# 1_Supply.net
KiCad netlist of a schematic drawn in Altium Designer
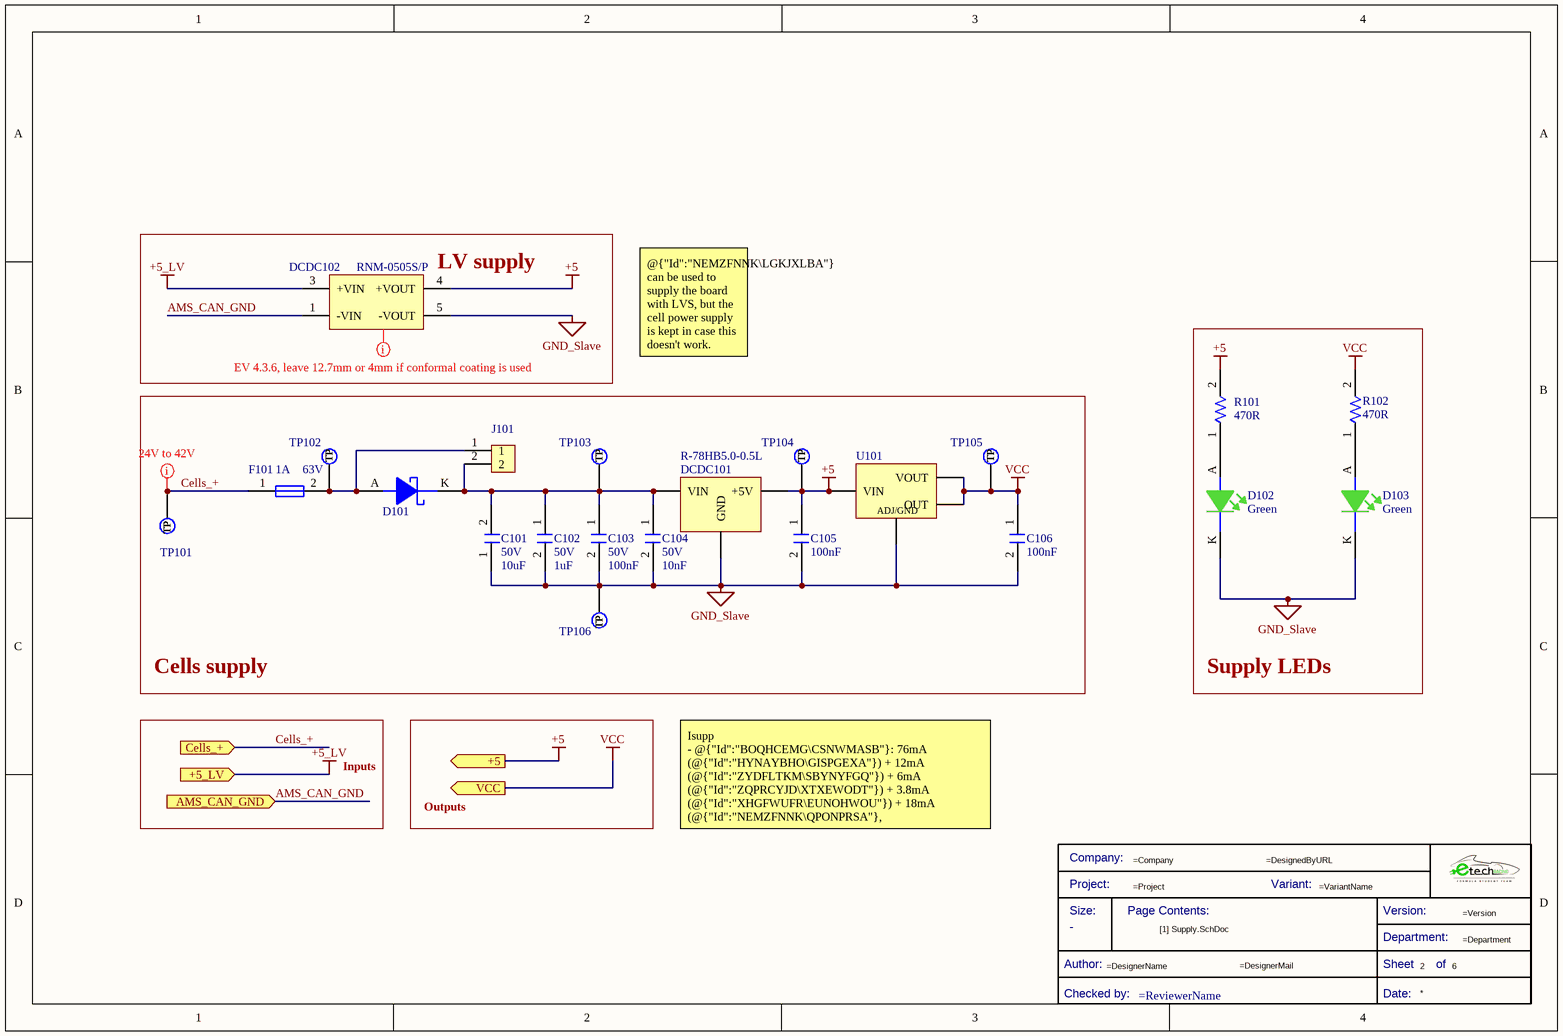
[diagram p0: [1] Supply.SchDoc]

(export (version "E")
  (design (tool "Eeschema 10.0.6"))
  (components
    (comp (ref "*")
      (value "Title Block_template")
      (description "Standard Title Block")
      (fields (field (name "SIZE") "-"))
      (libsource (lib "e-Tech_Racing") (part "Title Block_template"))
    )
    (comp (ref "C101")
      (value "GRJ32ER71H106KE11L")
      (footprint "C10u-50V-1210FNPMLCC-X7R")
      (description "Multilayer Ceramic Capacitors MLCC - SMD/SMT 1210 10uF 50volts X7R +/-10% Soft Term")
      (fields
        (field (name "MANUFACTURER") "Murata")
        (field (name "VOLTAGE RATING") "50V")
        (field (name "TOLERANCE") "10%")
        (field (name "CAPACITANCE") "10uF")
        (field (name ".CREATOR") "DR")
      )
      (libsource (lib "Passives") (part "C10u-50V-1210FNPMLCC-X7R"))
    )
    (comp (ref "C102")
      (value "885012207103")
      (footprint "C0805FNPC-R")
      (fields
        (field (name "VOLTAGE RATING") "50V")
        (field (name "TOLERANCE") "10%")
        (field (name "CAPACITANCE") "1uF")
        (field (name ".CREATOR") "GP")
      )
      (libsource (lib "Passives") (part "C1u-50V-0805FNPC-X7R"))
    )
    (comp (ref "C103")
      (value "885012207098")
      (footprint "C0805FNPC-R")
      (description "Cap, 0.1ΜF, 50V, 10%, X7R, 0805")
      (fields
        (field (name "VOLTAGE RATING") "50V")
        (field (name "TOLERANCE") "10%")
        (field (name "CAPACITANCE") "100nF")
        (field (name ".CREATOR") "DR")
      )
      (libsource (lib "Passives") (part "C100n-50V-0805FNPC-X7R"))
    )
    (comp (ref "C104")
      (value "885012207092")
      (footprint "C0805FNPC-R")
      (description "Cap, 0.01ΜF, 50V, 10%, X7R, 0805")
      (fields
        (field (name "VOLTAGE RATING") "50V")
        (field (name "TOLERANCE") "10%")
        (field (name "CAPACITANCE") "10nF")
        (field (name ".CREATOR") "DR")
      )
      (libsource (lib "Passives") (part "C10n-50V-0805FNPC-X7R"))
    )
    (comp (ref "C105")
      (value "885012207098")
      (footprint "C0805FNPC-R")
      (description "Cap, 0.1ΜF, 50V, 10%, X7R, 0805")
      (fields
        (field (name "TOLERANCE") "10%")
        (field (name "CAPACITANCE") "100nF")
        (field (name ".CREATOR") "DR")
      )
      (libsource (lib "Passives") (part "C100n-50V-0805FNPC-X7R"))
    )
    (comp (ref "C106")
      (value "885012207098")
      (footprint "C0805FNPC-R")
      (description "Cap, 0.1ΜF, 50V, 10%, X7R, 0805")
      (fields
        (field (name "TOLERANCE") "10%")
        (field (name "CAPACITANCE") "100nF")
        (field (name ".CREATOR") "DR")
      )
      (libsource (lib "Passives") (part "C100n-50V-0805FNPC-X7R"))
    )
    (comp (ref "D101")
      (value "MBR0530")
      (footprint "DSC-SOD123")
      (description "VR=30V IF=500mA 30pF P=410mW")
      (fields (field (name ".CREATOR") "GP"))
      (libsource (lib "Filter components") (part "DSC-0.5/30-SOD123"))
    )
    (comp (ref "D102")
      (value "150080VS75000")
      (footprint "LED_0805_WE")
      (description "Led, Green, 570 Nm, 2 V, 30 Ma, 40 Mcd Rohs Compliant: Yes")
      (fields (field (name "COLOR") "Green") (field (name ".CREATOR") "DR"))
      (libsource (lib "Semiconductor") (part "LEDVS-0805-40"))
    )
    (comp (ref "D103")
      (value "150080VS75000")
      (footprint "LED_0805_WE")
      (description "Led, Green, 570 Nm, 2 V, 30 Ma, 40 Mcd Rohs Compliant: Yes")
      (fields (field (name "COLOR") "Green") (field (name ".CREATOR") "DR"))
      (libsource (lib "Semiconductor") (part "LEDVS-0805-40"))
    )
    (comp (ref "DCDC101")
      (value "R-78HB5.0-0.5L")
      (footprint "DCDC_Slaves")
      (description "0.5A DC/DC-Converter 'INNOLINE' SIP3 reg; V. In: 9-72; V. Out: 5.0; mA. Out: 500")
      (fields (field (name ".CREATOR") "DR"))
      (libsource (lib "Semiconductor") (part "DCDC-72V/5V-0.5A"))
    )
    (comp (ref "DCDC102")
      (value "RNM-0505S/P")
      (footprint "DCDC_RNM-0505S/P")
      (description "1W DC/DC-Converter 'ECONOLINE' DIP6 1kV unreg; V. In: 05; V. Out: 05; mA. Out: 200")
      (fields
        (field (name "MANUFACTURER") "Recom")
        (field (name "MANUFACTURER PART NUMBER") "RNM-0505S/P")
        (field (name ".CREATOR") "GP")
      )
      (libsource (lib "Semiconductor") (part "DCDC_RNM-0505S/P"))
    )
    (comp (ref "F101")
      (value "0437001.WRA")
      (footprint "Fuse_1206")
      (description "Fuse Chip Fast Acting 1A 63V SMD Solder Pad 1206 Ceramic T/R Automotive")
      (fields
        (field (name "MANUFACTURER") "Littelfuse")
        (field (name "CURRENT RATING") "1A")
        (field (name "VOLTAGE RATING (DC)") "63V")
        (field (name ".CREATOR") "DO")
      )
      (libsource (lib "Filter components") (part "Fuse_1A_63V_1206"))
    )
    (comp (ref "J101")
      (value "61300211121")
      (footprint "J_Pinheader_1x2")
      (description "CONN HEADER 2 POS 2.54")
      (fields (field (name "MANUFACTURER") "Molex") (field (name ".CREATOR") "GP"))
      (libsource (lib "Electromechanical") (part "J_Jumper"))
    )
    (comp (ref "R101")
      (value "CR0805-FX-4700GLF")
      (footprint "R0805FTK")
      (description "Res Thick Film 0805 470 Ohm 1% 1/8W ±100ppm/°C Molded SMD SMD Paper Tape on Plastic Reel")
      (fields
        (field (name "TOLERANCE") "1%")
        (field (name "RESISTANCE") "470R")
        (field (name ".CREATOR") "DR")
      )
      (libsource (lib "Passives") (part "R470-0805FTK"))
    )
    (comp (ref "R102")
      (value "CR0805-FX-4700GLF")
      (footprint "R0805FTK")
      (description "Res Thick Film 0805 470 Ohm 1% 1/8W ±100ppm/°C Molded SMD SMD Paper Tape on Plastic Reel")
      (fields
        (field (name "TOLERANCE") "1%")
        (field (name "RESISTANCE") "470R")
        (field (name ".CREATOR") "DR")
      )
      (libsource (lib "Passives") (part "R470-0805FTK"))
    )
    (comp (ref "TP101")
      (value "TestPoint")
      (footprint "TestPoint")
      (description "Test Point 1x1 mm")
      (fields (field (name ".CREATOR") "GP") (field (name ".PCBCHECK") "GP") (field (name ".SCHCHECK") "GP"))
      (libsource (lib "e-Tech_Racing") (part "TestPoint"))
    )
    (comp (ref "TP102")
      (value "TestPoint")
      (footprint "TestPoint")
      (description "Test Point 1x1 mm")
      (fields (field (name ".CREATOR") "GP") (field (name ".PCBCHECK") "GP") (field (name ".SCHCHECK") "GP"))
      (libsource (lib "e-Tech_Racing") (part "TestPoint"))
    )
    (comp (ref "TP103")
      (value "TestPoint")
      (footprint "TestPoint")
      (description "Test Point 1x1 mm")
      (fields (field (name ".CREATOR") "GP") (field (name ".PCBCHECK") "GP") (field (name ".SCHCHECK") "GP"))
      (libsource (lib "e-Tech_Racing") (part "TestPoint"))
    )
    (comp (ref "TP104")
      (value "TestPoint")
      (footprint "TestPoint")
      (description "Test Point 1x1 mm")
      (fields (field (name ".CREATOR") "GP") (field (name ".PCBCHECK") "GP") (field (name ".SCHCHECK") "GP"))
      (libsource (lib "e-Tech_Racing") (part "TestPoint"))
    )
    (comp (ref "TP105")
      (value "TestPoint")
      (footprint "TestPoint")
      (description "Test Point 1x1 mm")
      (fields (field (name ".CREATOR") "GP") (field (name ".PCBCHECK") "GP") (field (name ".SCHCHECK") "GP"))
      (libsource (lib "e-Tech_Racing") (part "TestPoint"))
    )
    (comp (ref "TP106")
      (value "TestPoint")
      (footprint "TestPoint")
      (description "Test Point 1x1 mm")
      (fields (field (name ".CREATOR") "GP") (field (name ".PCBCHECK") "GP") (field (name ".SCHCHECK") "GP"))
      (libsource (lib "e-Tech_Racing") (part "TestPoint"))
    )
    (comp (ref "U101")
      (value "LM1117IMP-3.3/NOPB")
      (footprint "LDO_10V-0.8/3V3-SOT223")
      (description "LDO Regulator Pos 3.3V 0.8A 4-Pin(3+Tab) SOT-223 T/R / IC REG LDO 3.3V 0.8A SOT223")
      (fields (field (name "MANUFACTURER") "Texas Instruments") (field (name ".CREATOR") "GP"))
      (libsource (lib "Semiconductor") (part "LDO_10V-0.8/3V3-SOT223"))
    )
  )
  (nets
    (net (code "1") (name "+5") (class "Default")
      (node (ref "C105") (pin "1") (pinfunction "1_1") (pintype "passive"))
      (node (ref "DCDC101") (pin "3") (pinfunction "+5V_3") (pintype "passive"))
      (node (ref "DCDC102") (pin "4") (pinfunction "+VOUT_4") (pintype "passive"))
      (node (ref "R101") (pin "2") (pinfunction "2_2") (pintype "passive"))
      (node (ref "TP104") (pin "1") (pinfunction "TP_1") (pintype "passive"))
      (node (ref "U101") (pin "3") (pinfunction "VIN_3") (pintype "passive"))
    )
    (net (code "2") (name "+5_LV") (class "Default")
      (node (ref "DCDC102") (pin "3") (pinfunction "+VIN_3") (pintype "passive"))
    )
    (net (code "3") (name "/AMS_CAN_GND") (class "Default")
      (node (ref "DCDC102") (pin "1") (pinfunction "-VIN_1") (pintype "passive"))
    )
    (net (code "4") (name "/Cells_+") (class "Default")
      (node (ref "F101") (pin "1") (pinfunction "1_1") (pintype "passive"))
      (node (ref "TP101") (pin "1") (pinfunction "TP_1") (pintype "passive"))
    )
    (net (code "5") (name "GND_Slave") (class "Default")
      (node (ref "C101") (pin "1") (pinfunction "1_1") (pintype "passive"))
      (node (ref "C102") (pin "2") (pinfunction "2_2") (pintype "passive"))
      (node (ref "C103") (pin "2") (pinfunction "2_2") (pintype "passive"))
      (node (ref "C104") (pin "2") (pinfunction "2_2") (pintype "passive"))
      (node (ref "C105") (pin "2") (pinfunction "2_2") (pintype "passive"))
      (node (ref "C106") (pin "2") (pinfunction "2_2") (pintype "passive"))
      (node (ref "D102") (pin "K") (pinfunction "K_K") (pintype "passive"))
      (node (ref "D103") (pin "K") (pinfunction "K_K") (pintype "passive"))
      (node (ref "DCDC101") (pin "2") (pinfunction "GND_2") (pintype "passive"))
      (node (ref "DCDC102") (pin "5") (pinfunction "-VOUT_5") (pintype "passive"))
      (node (ref "TP106") (pin "1") (pinfunction "TP_1") (pintype "passive"))
      (node (ref "U101") (pin "1") (pinfunction "ADJ/GND_1") (pintype "passive"))
    )
    (net (code "6") (name "Net-(D102-PadA)") (class "Default")
      (node (ref "D102") (pin "A") (pinfunction "A_A") (pintype "passive"))
      (node (ref "R101") (pin "1") (pinfunction "1_1") (pintype "passive"))
    )
    (net (code "7") (name "Net-(D103-PadA)") (class "Default")
      (node (ref "D103") (pin "A") (pinfunction "A_A") (pintype "passive"))
      (node (ref "R102") (pin "1") (pinfunction "1_1") (pintype "passive"))
    )
    (net (code "8") (name "Net-(DCDC101-VIN)") (class "Default")
      (node (ref "C101") (pin "2") (pinfunction "2_2") (pintype "passive"))
      (node (ref "C102") (pin "1") (pinfunction "1_1") (pintype "passive"))
      (node (ref "C103") (pin "1") (pinfunction "1_1") (pintype "passive"))
      (node (ref "C104") (pin "1") (pinfunction "1_1") (pintype "passive"))
      (node (ref "D101") (pin "K") (pinfunction "K_K") (pintype "passive"))
      (node (ref "DCDC101") (pin "1") (pinfunction "VIN_1") (pintype "passive"))
      (node (ref "J101") (pin "2") (pinfunction "2_2") (pintype "passive"))
      (node (ref "TP103") (pin "1") (pinfunction "TP_1") (pintype "passive"))
    )
    (net (code "9") (name "Net-(TP102-TP)") (class "Default")
      (node (ref "D101") (pin "A") (pinfunction "A_A") (pintype "passive"))
      (node (ref "F101") (pin "2") (pinfunction "2_2") (pintype "passive"))
      (node (ref "J101") (pin "1") (pinfunction "1_1") (pintype "passive"))
      (node (ref "TP102") (pin "1") (pinfunction "TP_1") (pintype "passive"))
    )
    (net (code "10") (name "VCC") (class "Default")
      (node (ref "C106") (pin "1") (pinfunction "1_1") (pintype "passive"))
      (node (ref "R102") (pin "2") (pinfunction "2_2") (pintype "passive"))
      (node (ref "TP105") (pin "1") (pinfunction "TP_1") (pintype "passive"))
      (node (ref "U101") (pin "2") (pinfunction "OUT_2") (pintype "passive"))
      (node (ref "U101") (pin "4") (pinfunction "VOUT_4") (pintype "passive"))
    )
  )
)
